# SCH_sx28ice_2022-10-07.net
KiCad netlist of a schematic drawn in EasyEDA
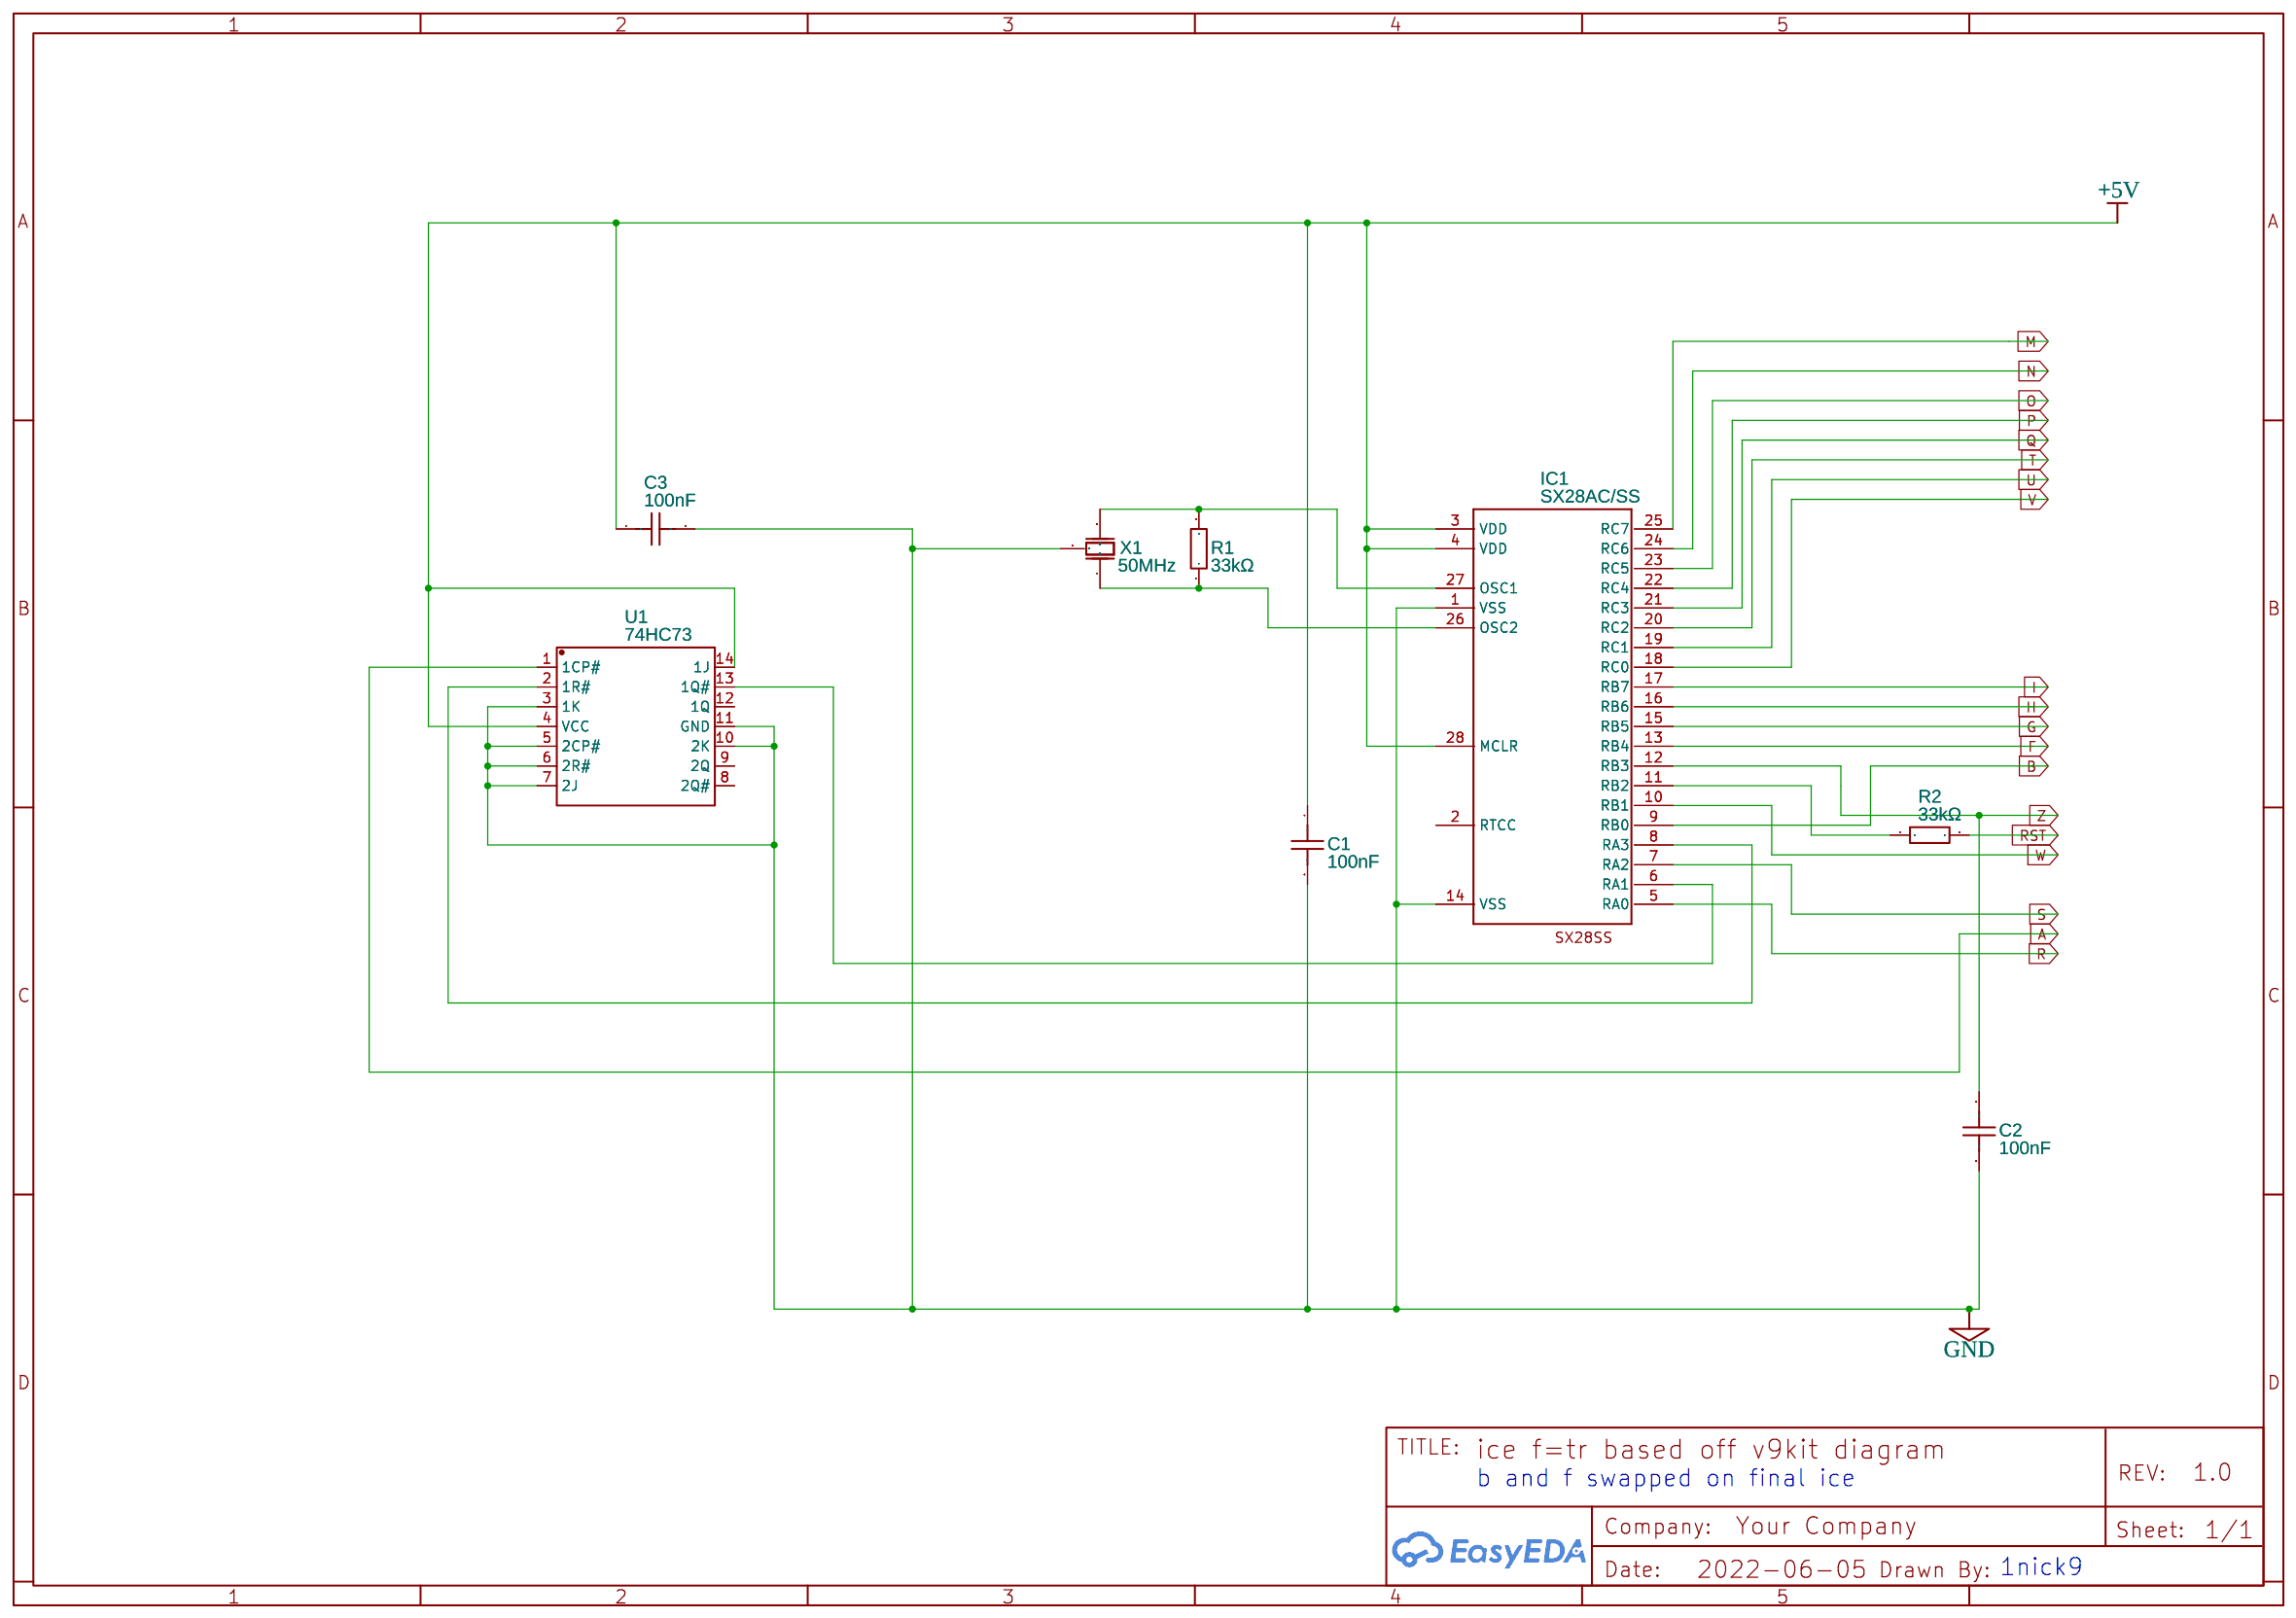
[diagram p0: schematic sheet]

(export (version "E")
  (design (tool "Eeschema 10.0.6"))
  (components
    (comp (ref "C1")
      (value "100nF")
      (fields
        (field (name "BOM_Manufacturer Part") "0603B104K250NT")
        (field (name "BOM_Supplier Part") "C694249")
      )
      (libsource (lib "") (part "0603B104K250NT"))
    )
    (comp (ref "C2")
      (value "100nF")
      (fields
        (field (name "BOM_Manufacturer Part") "0603B104K250NT")
        (field (name "BOM_Supplier Part") "C694249")
      )
      (libsource (lib "") (part "0603B104K250NT"))
    )
    (comp (ref "C3")
      (value "100nF")
      (fields
        (field (name "BOM_Manufacturer Part") "0603B104K250NT")
        (field (name "BOM_Supplier Part") "C694249")
      )
      (libsource (lib "") (part "0603B104K250NT_1"))
    )
    (comp (ref "IC1") (value "SX28AC/SS") (libsource (lib "") (part "SX28AC/SS")))
    (comp (ref "R1")
      (value "33kΩ")
      (fields
        (field (name "BOM_Manufacturer Part") "RMC060333K1%N")
        (field (name "BOM_Supplier Part") "C269485")
      )
      (libsource (lib "") (part "RMC060333K1%N"))
    )
    (comp (ref "R2")
      (value "33kΩ")
      (fields
        (field (name "BOM_Manufacturer Part") "RMC060333K1%N")
        (field (name "BOM_Supplier Part") "C269485")
      )
      (libsource (lib "") (part "RMC060333K1%N_1"))
    )
    (comp (ref "U1")
      (value "74HC73")
      (fields
        (field (name "BOM_Manufacturer Part") "CD74HC73M96")
        (field (name "BOM_Supplier Part") "C350539")
      )
      (libsource (lib "") (part "CD74HC73M96"))
    )
    (comp (ref "X1") (value "50MHz") (libsource (lib "") (part "CSTNR4M00GH5L000R0")))
  )
  (nets
    (net (code "1") (name "+5V") (class "Default")
      (node (ref "C1") (pin "1") (pinfunction "1_1") (pintype "unspecified"))
      (node (ref "C3") (pin "1") (pinfunction "1_1") (pintype "unspecified"))
      (node (ref "IC1") (pin "28") (pinfunction "MCLR_28") (pintype "bidirectional"))
      (node (ref "IC1") (pin "3") (pinfunction "VDD_3") (pintype "bidirectional"))
      (node (ref "IC1") (pin "4") (pinfunction "VDD_4") (pintype "bidirectional"))
      (node (ref "U1") (pin "14") (pinfunction "1J_14") (pintype "unspecified"))
      (node (ref "U1") (pin "4") (pinfunction "VCC_4") (pintype "unspecified"))
    )
    (net (code "2") (name "A") (class "Default")
      (node (ref "U1") (pin "1") (pinfunction "1CP#_1") (pintype "unspecified"))
    )
    (net (code "3") (name "B") (class "Default")
      (node (ref "IC1") (pin "9") (pinfunction "RB0_9") (pintype "bidirectional"))
    )
    (net (code "4") (name "F") (class "Default")
      (node (ref "IC1") (pin "13") (pinfunction "RB4_13") (pintype "bidirectional"))
    )
    (net (code "5") (name "G") (class "Default")
      (node (ref "IC1") (pin "15") (pinfunction "RB5_15") (pintype "bidirectional"))
    )
    (net (code "6") (name "GND") (class "Default")
      (node (ref "C1") (pin "2") (pinfunction "2_2") (pintype "unspecified"))
      (node (ref "C2") (pin "2") (pinfunction "2_2") (pintype "unspecified"))
      (node (ref "C3") (pin "2") (pinfunction "2_2") (pintype "unspecified"))
      (node (ref "IC1") (pin "1") (pinfunction "VSS_1") (pintype "bidirectional"))
      (node (ref "IC1") (pin "14") (pinfunction "VSS_14") (pintype "bidirectional"))
      (node (ref "U1") (pin "10") (pinfunction "2K_10") (pintype "unspecified"))
      (node (ref "U1") (pin "11") (pinfunction "GND_11") (pintype "unspecified"))
      (node (ref "U1") (pin "3") (pinfunction "1K_3") (pintype "unspecified"))
      (node (ref "U1") (pin "5") (pinfunction "2CP#_5") (pintype "unspecified"))
      (node (ref "U1") (pin "6") (pinfunction "2R#_6") (pintype "unspecified"))
      (node (ref "U1") (pin "7") (pinfunction "2J_7") (pintype "unspecified"))
      (node (ref "X1") (pin "2") (pinfunction "GND_2") (pintype "input"))
    )
    (net (code "7") (name "H") (class "Default")
      (node (ref "IC1") (pin "16") (pinfunction "RB6_16") (pintype "bidirectional"))
    )
    (net (code "8") (name "I") (class "Default")
      (node (ref "IC1") (pin "17") (pinfunction "RB7_17") (pintype "bidirectional"))
    )
    (net (code "9") (name "M") (class "Default")
      (node (ref "IC1") (pin "25") (pinfunction "RC7_25") (pintype "bidirectional"))
    )
    (net (code "10") (name "N") (class "Default")
      (node (ref "IC1") (pin "24") (pinfunction "RC6_24") (pintype "bidirectional"))
    )
    (net (code "11") (name "Net-(IC1-OSC1)") (class "Default")
      (node (ref "IC1") (pin "27") (pinfunction "OSC1_27") (pintype "bidirectional"))
      (node (ref "R1") (pin "2") (pinfunction "2_2") (pintype "unspecified"))
      (node (ref "X1") (pin "3") (pinfunction "OSC2_3") (pintype "input"))
    )
    (net (code "12") (name "Net-(IC1-OSC2)") (class "Default")
      (node (ref "IC1") (pin "26") (pinfunction "OSC2_26") (pintype "bidirectional"))
      (node (ref "R1") (pin "1") (pinfunction "1_1") (pintype "unspecified"))
      (node (ref "X1") (pin "1") (pinfunction "OSC1_1") (pintype "input"))
    )
    (net (code "13") (name "Net-(IC1-RA1)") (class "Default")
      (node (ref "IC1") (pin "6") (pinfunction "RA1_6") (pintype "bidirectional"))
      (node (ref "U1") (pin "13") (pinfunction "1Q#_13") (pintype "unspecified"))
    )
    (net (code "14") (name "Net-(IC1-RA3)") (class "Default")
      (node (ref "IC1") (pin "8") (pinfunction "RA3_8") (pintype "bidirectional"))
      (node (ref "U1") (pin "2") (pinfunction "1R#_2") (pintype "unspecified"))
    )
    (net (code "15") (name "Net-(IC1-RB2)") (class "Default")
      (node (ref "IC1") (pin "11") (pinfunction "RB2_11") (pintype "bidirectional"))
      (node (ref "R2") (pin "1") (pinfunction "1_1") (pintype "unspecified"))
    )
    (net (code "16") (name "O") (class "Default")
      (node (ref "IC1") (pin "23") (pinfunction "RC5_23") (pintype "bidirectional"))
    )
    (net (code "17") (name "P") (class "Default")
      (node (ref "IC1") (pin "22") (pinfunction "RC4_22") (pintype "bidirectional"))
    )
    (net (code "18") (name "Q") (class "Default")
      (node (ref "IC1") (pin "21") (pinfunction "RC3_21") (pintype "bidirectional"))
    )
    (net (code "19") (name "R") (class "Default")
      (node (ref "IC1") (pin "5") (pinfunction "RA0_5") (pintype "bidirectional"))
    )
    (net (code "20") (name "RST") (class "Default")
      (node (ref "R2") (pin "2") (pinfunction "2_2") (pintype "unspecified"))
    )
    (net (code "21") (name "S") (class "Default")
      (node (ref "IC1") (pin "7") (pinfunction "RA2_7") (pintype "bidirectional"))
    )
    (net (code "22") (name "T") (class "Default")
      (node (ref "IC1") (pin "20") (pinfunction "RC2_20") (pintype "bidirectional"))
    )
    (net (code "23") (name "U") (class "Default")
      (node (ref "IC1") (pin "19") (pinfunction "RC1_19") (pintype "bidirectional"))
    )
    (net (code "24") (name "V") (class "Default")
      (node (ref "IC1") (pin "18") (pinfunction "RC0_18") (pintype "bidirectional"))
    )
    (net (code "25") (name "W") (class "Default")
      (node (ref "IC1") (pin "10") (pinfunction "RB1_10") (pintype "bidirectional"))
    )
    (net (code "26") (name "Z") (class "Default")
      (node (ref "C2") (pin "1") (pinfunction "1_1") (pintype "unspecified"))
      (node (ref "IC1") (pin "12") (pinfunction "RB3_12") (pintype "bidirectional"))
    )
    (net (code "27") (name "unconnected-(IC1-RTCC-Pad2)") (class "Default")
      (node (ref "IC1") (pin "2") (pinfunction "RTCC_2") (pintype "bidirectional"))
    )
    (net (code "28") (name "unconnected-(U1-1Q-Pad12)") (class "Default")
      (node (ref "U1") (pin "12") (pinfunction "1Q_12") (pintype "unspecified"))
    )
    (net (code "29") (name "unconnected-(U1-2Q#-Pad8)") (class "Default")
      (node (ref "U1") (pin "8") (pinfunction "2Q#_8") (pintype "unspecified"))
    )
    (net (code "30") (name "unconnected-(U1-2Q-Pad9)") (class "Default")
      (node (ref "U1") (pin "9") (pinfunction "2Q_9") (pintype "unspecified"))
    )
  )
)
